# ESP32_CAN_V2-usb.net
KiCad netlist of a schematic drawn in Altium Designer
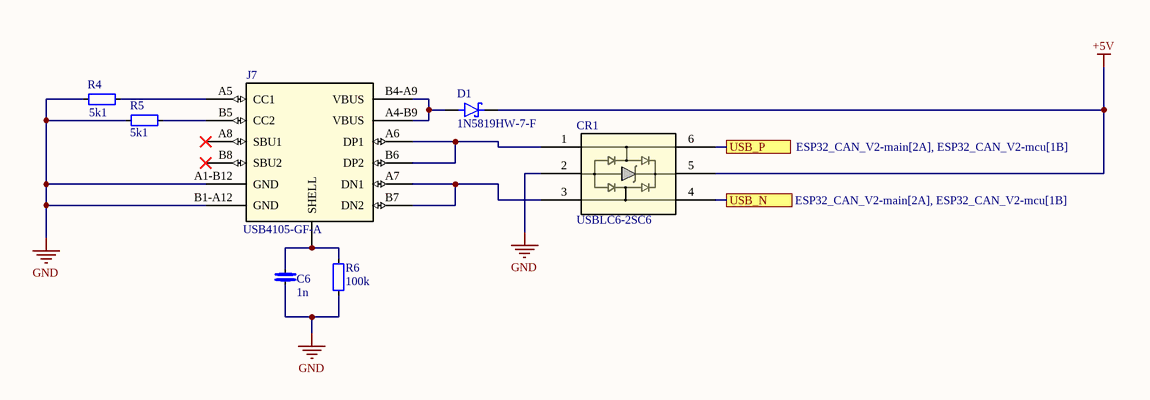
[diagram p0: ESP32_CAN_V2-usb.SchDoc]

(export (version "E")
  (design (tool "Eeschema 10.0.6"))
  (components
    (comp (ref "C6") (value "1n") (footprint "C0603") (libsource (lib "ESP32_CAN_V2") (part "C")))
    (comp (ref "CR1")
      (value "USBLC6-2SC6")
      (footprint "SOT23-6L_STM")
      (description "ESD Protection for USB 2.0 High Speed")
      (fields (field (name "COPYRIGHT") "Copyright (C) 2025 Ultra Librarian. All rights reserved."))
      (libsource (lib "ESP32_CAN_V2") (part "USBLC6-2SC6"))
    )
    (comp (ref "D1")
      (value "1N5819HW-7-F")
      (footprint "SOD3715X145N")
      (description "Diode Schottky 40 V 1A Surface Mount SOD-123")
      (fields (field (name "MF") "Diodes Inc."))
      (libsource (lib "ESP32_CAN_V2") (part "1N5819HW-7-F"))
    )
    (comp (ref "J7")
      (value "USB4105-GF-A")
      (footprint "USB4105_GCT")
      (description "Description")
      (fields (field (name "COPYRIGHT") "Copyright (C) 2025 Ultra Librarian. All rights reserved."))
      (libsource (lib "ESP32_CAN_V2") (part "USB4105-GF-A"))
    )
    (comp (ref "R4") (value "5k1") (footprint "R0603") (libsource (lib "ESP32_CAN_V2") (part "R")))
    (comp (ref "R5") (value "5k1") (footprint "R0603") (libsource (lib "ESP32_CAN_V2") (part "R")))
    (comp (ref "R6") (value "100k") (footprint "R0603") (libsource (lib "ESP32_CAN_V2") (part "R")))
  )
  (nets
    (net (code "1") (name "+5V") (class "Default")
      (node (ref "CR1") (pin "5") (pinfunction "5_5") (pintype "passive"))
      (node (ref "D1") (pin "C") (pinfunction "K_C") (pintype "passive"))
    )
    (net (code "2") (name "/USB_N") (class "Default")
      (node (ref "CR1") (pin "4") (pinfunction "4_4") (pintype "passive"))
    )
    (net (code "3") (name "/USB_P") (class "Default")
      (node (ref "CR1") (pin "6") (pinfunction "6_6") (pintype "passive"))
    )
    (net (code "4") (name "GND") (class "Default")
      (node (ref "C6") (pin "1") (pinfunction "1_1") (pintype "passive"))
      (node (ref "CR1") (pin "2") (pinfunction "2_2") (pintype "passive"))
      (node (ref "J7") (pin "A1-B12") (pinfunction "GND_A1-B12") (pintype "power_in"))
      (node (ref "J7") (pin "B1-A12") (pinfunction "GND_B1-A12") (pintype "power_in"))
      (node (ref "R4") (pin "1") (pinfunction "0_1") (pintype "passive"))
      (node (ref "R5") (pin "1") (pinfunction "0_1") (pintype "passive"))
      (node (ref "R6") (pin "1") (pinfunction "0_1") (pintype "passive"))
    )
    (net (code "5") (name "Net-(D1-PadA)") (class "Default")
      (node (ref "D1") (pin "A") (pinfunction "A_A") (pintype "passive"))
      (node (ref "J7") (pin "A4-B9") (pinfunction "VBUS_A4-B9") (pintype "power_in"))
      (node (ref "J7") (pin "B4-A9") (pinfunction "VBUS_B4-A9") (pintype "power_in"))
    )
    (net (code "6") (name "Net-(J7-CC1)") (class "Default")
      (node (ref "J7") (pin "A5") (pinfunction "CC1_A5") (pintype "bidirectional"))
      (node (ref "R4") (pin "2") (pinfunction "1_2") (pintype "passive"))
    )
    (net (code "7") (name "Net-(J7-CC2)") (class "Default")
      (node (ref "J7") (pin "B5") (pinfunction "CC2_B5") (pintype "bidirectional"))
      (node (ref "R5") (pin "2") (pinfunction "1_2") (pintype "passive"))
    )
    (net (code "8") (name "Net-(J7-DN1)") (class "Default")
      (node (ref "CR1") (pin "3") (pinfunction "3_3") (pintype "passive"))
      (node (ref "J7") (pin "A7") (pinfunction "DN1_A7") (pintype "bidirectional"))
      (node (ref "J7") (pin "B7") (pinfunction "DN2_B7") (pintype "bidirectional"))
    )
    (net (code "9") (name "Net-(J7-DP1)") (class "Default")
      (node (ref "CR1") (pin "1") (pinfunction "1_1") (pintype "passive"))
      (node (ref "J7") (pin "A6") (pinfunction "DP1_A6") (pintype "bidirectional"))
      (node (ref "J7") (pin "B6") (pinfunction "DP2_B6") (pintype "bidirectional"))
    )
    (net (code "10") (name "Net-(R6-1)") (class "Default")
      (node (ref "C6") (pin "2") (pinfunction "2_2") (pintype "passive"))
      (node (ref "J7") (pin "SHELL") (pinfunction "SHELL_SHELL") (pintype "passive"))
      (node (ref "R6") (pin "2") (pinfunction "1_2") (pintype "passive"))
    )
    (net (code "11") (name "unconnected-(J7-SBU1-PadA8)") (class "Default")
      (node (ref "J7") (pin "A8") (pinfunction "SBU1_A8") (pintype "bidirectional+no_connect"))
    )
    (net (code "12") (name "unconnected-(J7-SBU2-PadB8)") (class "Default")
      (node (ref "J7") (pin "B8") (pinfunction "SBU2_B8") (pintype "bidirectional+no_connect"))
    )
  )
)
